# EEM_FMC_Carrier.net
KiCad netlist of a schematic drawn in Altium Designer
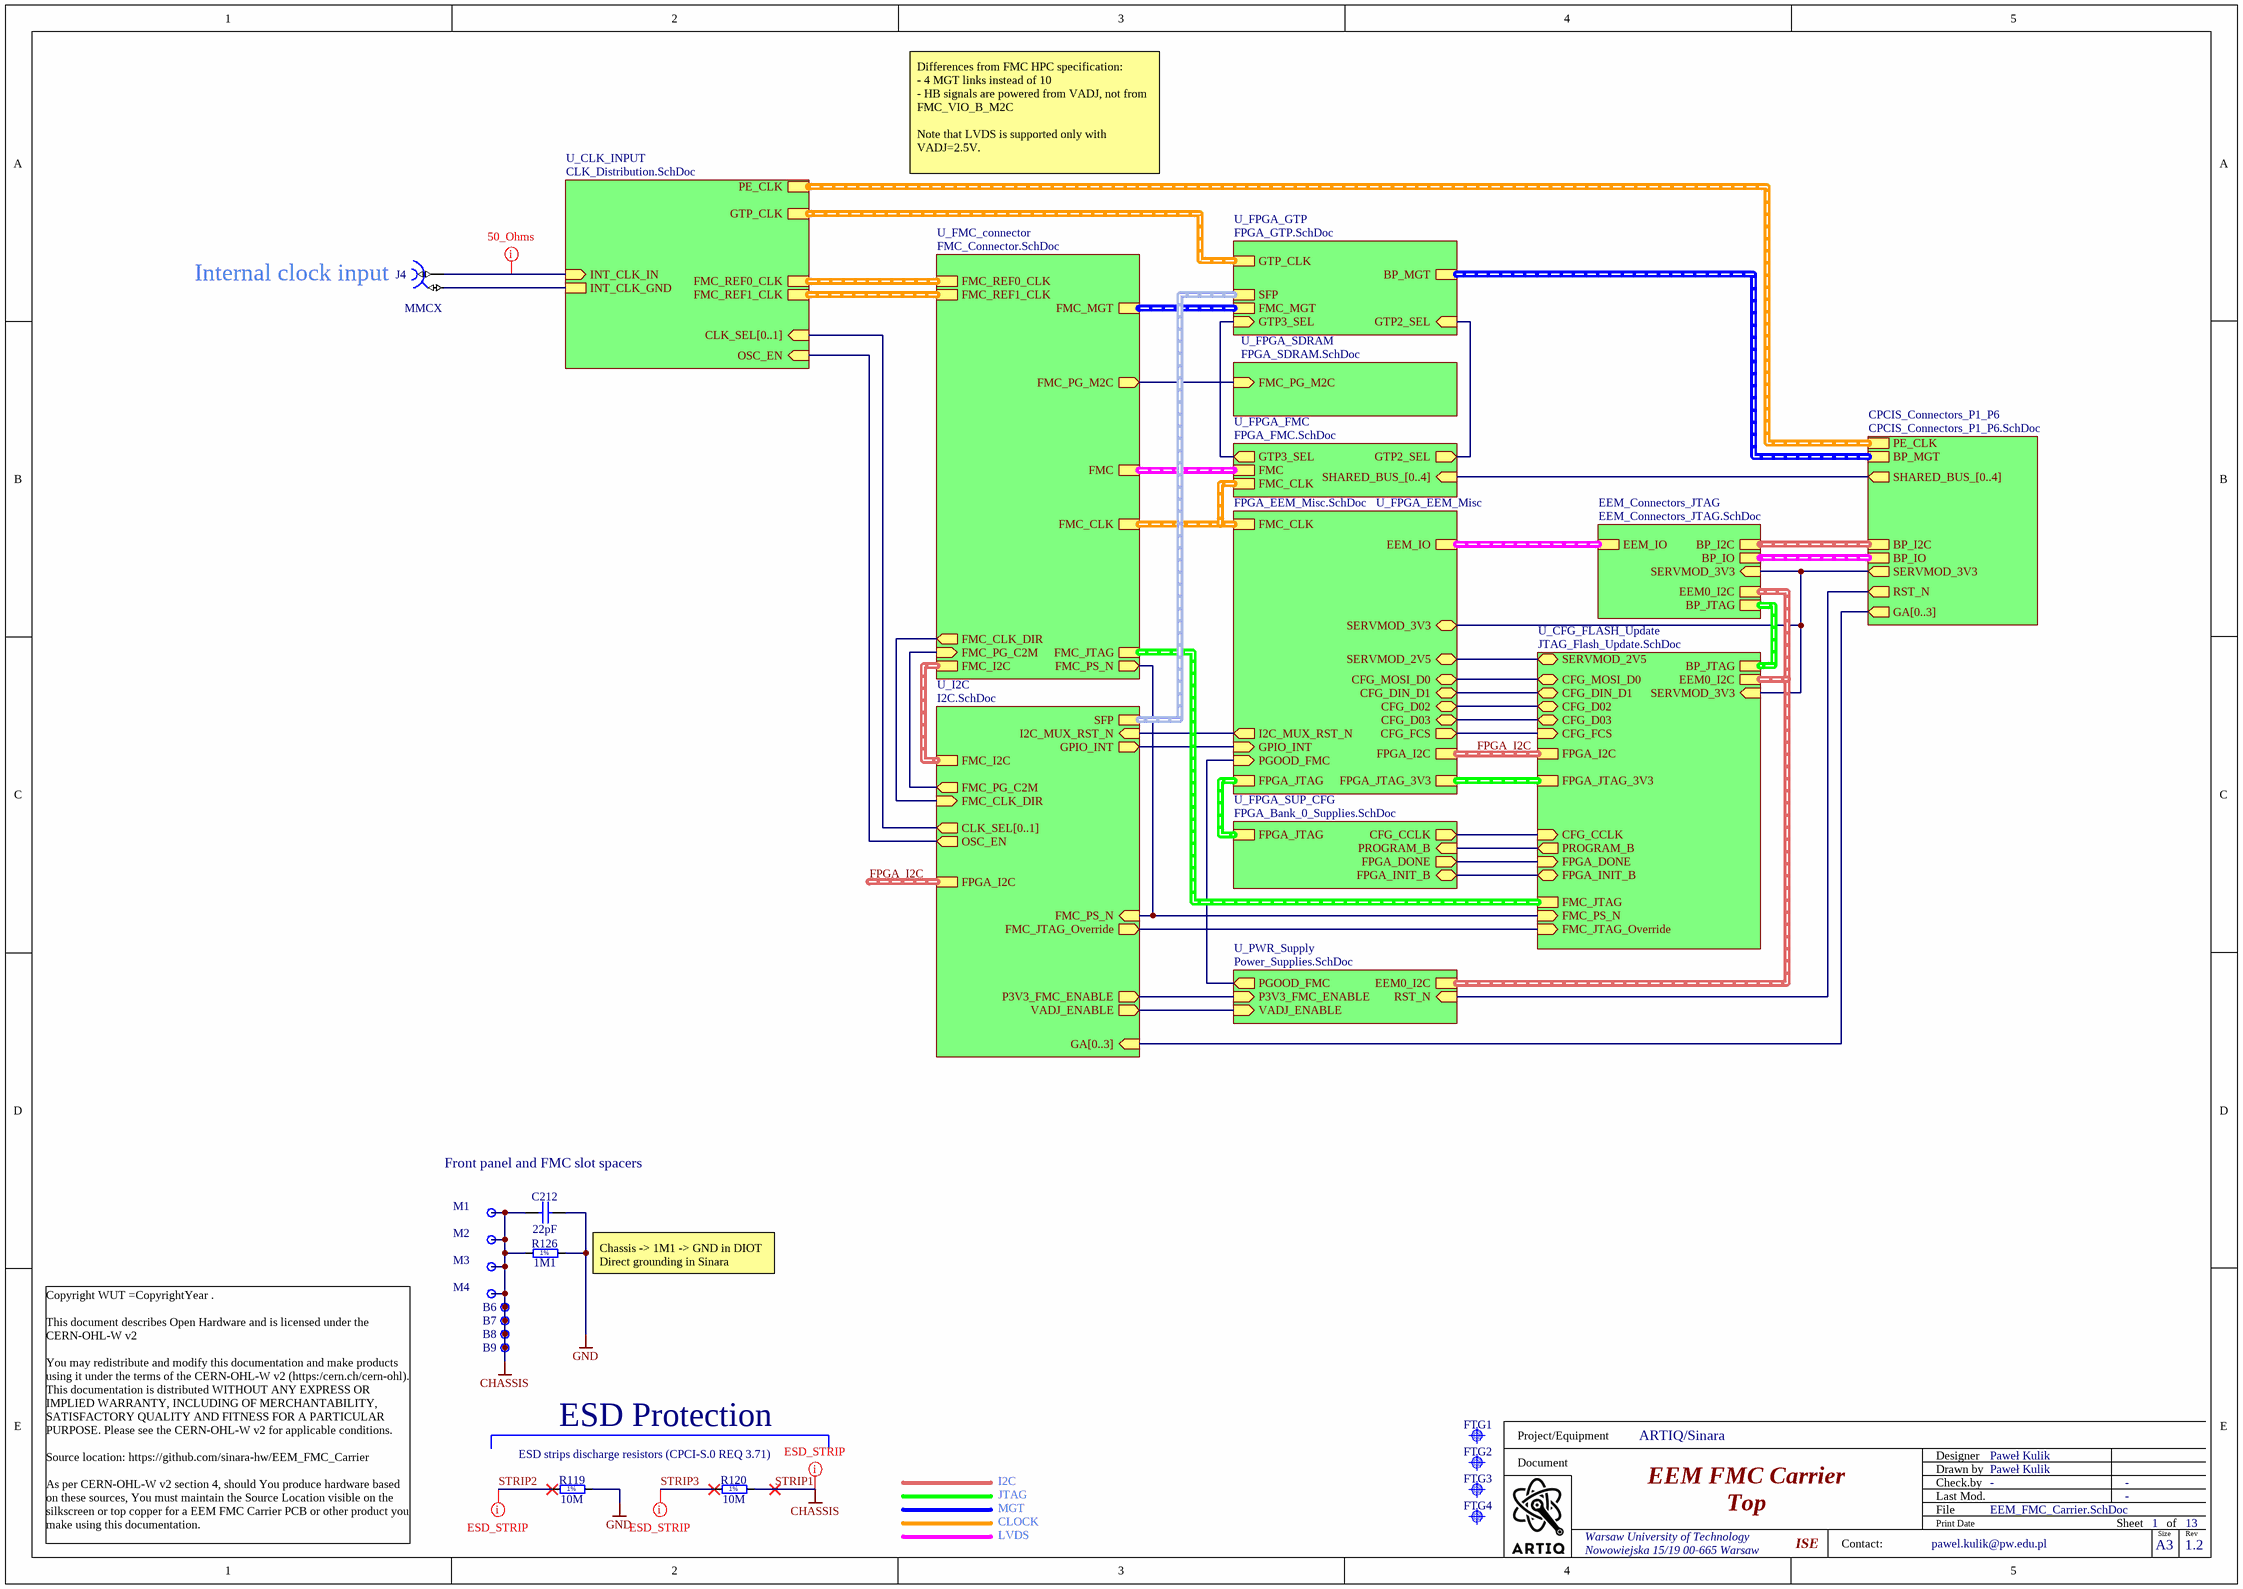
[diagram p0: EEM_FMC_Carrier.SchDoc]

(export (version "E")
  (design (tool "Eeschema 10.0.6"))
  (components
    (comp (ref "B6")
      (value "Plated Hole")
      (footprint "MTG270_500")
      (description "Single Terminal Socket")
      (fields (field (name "PART NUMBER") "PLATED_HOLE2.7_PAD5.0") (field (name "AUTHOR") "CERN DEM JMW"))
      (libsource (lib "Eletro-mechanical") (part "Single Terminal Socket"))
    )
    (comp (ref "B7")
      (value "Plated Hole")
      (footprint "MTG270_500")
      (description "Single Terminal Socket")
      (fields (field (name "PART NUMBER") "PLATED_HOLE2.7_PAD5.0") (field (name "AUTHOR") "CERN DEM JMW"))
      (libsource (lib "Eletro-mechanical") (part "Single Terminal Socket"))
    )
    (comp (ref "B8")
      (value "Plated Hole")
      (footprint "MTG270_500")
      (description "Single Terminal Socket")
      (fields (field (name "PART NUMBER") "PLATED_HOLE2.7_PAD5.0") (field (name "AUTHOR") "CERN DEM JMW"))
      (libsource (lib "Eletro-mechanical") (part "Single Terminal Socket"))
    )
    (comp (ref "B9")
      (value "Plated Hole")
      (footprint "MTG270_500")
      (description "Single Terminal Socket")
      (fields (field (name "PART NUMBER") "PLATED_HOLE2.7_PAD5.0") (field (name "AUTHOR") "CERN DEM JMW"))
      (libsource (lib "Eletro-mechanical") (part "Single Terminal Socket"))
    )
    (comp (ref "C212")
      (value "22pF")
      (footprint "CAPC1005X55N")
      (description "Non-polarised capacitor")
      (fields
        (field (name "PART NUMBER") "CC0402_22PF_50V_5%_C0G")
        (field (name "VOLTAGE") "50V")
        (field (name "AUTHOR") "CERN DEM JLC")
      )
      (libsource (lib "Capacitors") (part "Capacitor - non polarized"))
    )
    (comp (ref "FTG1")
      (value "Use only in PCB")
      (footprint "FIDUCIAL_TOP_C100-200")
      (description "Fiducial Target")
      (fields (field (name "PART NUMBER") "FIDUCIAL_TARGET_C100-200") (field (name "AUTHOR") "CERN DEM JLC"))
      (libsource (lib "Eletro-mechanical") (part "Fiducial Target"))
    )
    (comp (ref "FTG2")
      (value "Use only in PCB")
      (footprint "FIDUCIAL_TOP_S100-200")
      (description "Fiducial Target")
      (fields (field (name "PART NUMBER") "FIDUCIAL_TARGET_S100-200") (field (name "AUTHOR") "CERN DEM JLC"))
      (libsource (lib "Eletro-mechanical") (part "Fiducial Target"))
    )
    (comp (ref "FTG3")
      (value "Use only in PCB")
      (footprint "FIDUCIAL_TOP_S100-200")
      (description "Fiducial Target")
      (fields (field (name "PART NUMBER") "FIDUCIAL_TARGET_S100-200") (field (name "AUTHOR") "CERN DEM JLC"))
      (libsource (lib "Eletro-mechanical") (part "Fiducial Target"))
    )
    (comp (ref "FTG4")
      (value "Use only in PCB")
      (footprint "FIDUCIAL_TOP_S100-200")
      (description "Fiducial Target")
      (fields (field (name "PART NUMBER") "FIDUCIAL_TARGET_S100-200") (field (name "AUTHOR") "CERN DEM JLC"))
      (libsource (lib "Eletro-mechanical") (part "Fiducial Target"))
    )
    (comp (ref "J4")
      (value "MMCX")
      (footprint "SAMTEC_MMCX-J-P-H-ST-TH1")
      (fields
        (field (name "PART NUMBER") "SAMTEC_MMCX-J-P-H-ST-TH1")
        (field (name "MANUFACTURER") "SAMTEC")
        (field (name "MANUFACTURER PART NUMBER") "MMCX-J-P-H-ST-TH1")
        (field (name "AUTHOR") "CERN DEM JLC")
      )
      (libsource (lib "Connectors") (part "Coax_1Female_1Shield"))
    )
    (comp (ref "M1")
      (value "Plated Hole")
      (footprint "MTG300_600")
      (description "Single Terminal Socket")
      (fields (field (name "PART NUMBER") "PLATED_HOLE3.0_PAD6.0") (field (name "AUTHOR") "CERN DEM JLC"))
      (libsource (lib "Eletro-mechanical") (part "Single Terminal Socket"))
    )
    (comp (ref "M2")
      (value "Plated Hole")
      (footprint "MTG300_600")
      (description "Single Terminal Socket")
      (fields (field (name "PART NUMBER") "PLATED_HOLE3.0_PAD6.0") (field (name "AUTHOR") "CERN DEM JLC"))
      (libsource (lib "Eletro-mechanical") (part "Single Terminal Socket"))
    )
    (comp (ref "M3")
      (value "Plated Hole")
      (footprint "MTG300_600")
      (description "Single Terminal Socket")
      (fields (field (name "PART NUMBER") "PLATED_HOLE3.0_PAD6.0") (field (name "AUTHOR") "CERN DEM JLC"))
      (libsource (lib "Eletro-mechanical") (part "Single Terminal Socket"))
    )
    (comp (ref "M4")
      (value "Plated Hole")
      (footprint "MTG300_600")
      (description "Single Terminal Socket")
      (fields (field (name "PART NUMBER") "PLATED_HOLE3.0_PAD6.0") (field (name "AUTHOR") "CERN DEM JLC"))
      (libsource (lib "Eletro-mechanical") (part "Single Terminal Socket"))
    )
    (comp (ref "R119")
      (value "10M")
      (footprint "RESC2113X55N")
      (description "Resistor - 1%")
      (fields
        (field (name "PART NUMBER") "R0805_10M_1%_0.125W_100PPM_VISHAY_CRCW e3")
        (field (name "POWER") "0.125W")
        (field (name "AUTHOR") "CERN DEM BC")
      )
      (libsource (lib "Resistors") (part "Resistor - 1%"))
    )
    (comp (ref "R120")
      (value "10M")
      (footprint "RESC2113X55N")
      (description "Resistor - 1%")
      (fields
        (field (name "PART NUMBER") "R0805_10M_1%_0.125W_100PPM_VISHAY_CRCW e3")
        (field (name "POWER") "0.125W")
        (field (name "AUTHOR") "CERN DEM BC")
      )
      (libsource (lib "Resistors") (part "Resistor - 1%"))
    )
    (comp (ref "R126")
      (value "1M1")
      (footprint "RESC2012X60N")
      (description "Resistor - 1%")
      (fields
        (field (name "PART NUMBER") "R0805_1M1_1%_0.125W_100PPM")
        (field (name "MANUFACTURER") "GENERIC")
        (field (name "AUTHOR") "CERN DEM JLC")
      )
      (libsource (lib "Resistors") (part "Resistor - 1%"))
    )
  )
  (nets
    (net (code "37") (name "/INT_CLK_GND") (class "Default")
      (node (ref "J4") (pin "2") (pinfunction "2_2") (pintype "bidirectional"))
    )
    (net (code "38") (name "/INT_CLK_IN") (class "Default")
      (node (ref "J4") (pin "1") (pinfunction "1_1") (pintype "bidirectional"))
    )
    (net (code "50") (name "/STRIP2") (class "Default")
      (node (ref "R119") (pin "1") (pinfunction "1_1") (pintype "passive+no_connect"))
    )
    (net (code "51") (name "/STRIP3") (class "Default")
      (node (ref "R120") (pin "1") (pinfunction "1_1") (pintype "passive+no_connect"))
    )
    (net (code "54") (name "CHASSIS") (class "Default")
      (node (ref "B6") (pin "1") (pinfunction "1_1") (pintype "bidirectional"))
      (node (ref "B7") (pin "1") (pinfunction "1_1") (pintype "bidirectional"))
      (node (ref "B8") (pin "1") (pinfunction "1_1") (pintype "bidirectional"))
      (node (ref "B9") (pin "1") (pinfunction "1_1") (pintype "bidirectional"))
      (node (ref "C212") (pin "1") (pinfunction "1_1") (pintype "passive"))
      (node (ref "M1") (pin "1") (pinfunction "1_1") (pintype "bidirectional"))
      (node (ref "M2") (pin "1") (pinfunction "1_1") (pintype "bidirectional"))
      (node (ref "M3") (pin "1") (pinfunction "1_1") (pintype "bidirectional"))
      (node (ref "M4") (pin "1") (pinfunction "1_1") (pintype "bidirectional"))
      (node (ref "R120") (pin "2") (pinfunction "2_2") (pintype "passive"))
      (node (ref "R126") (pin "1") (pinfunction "1_1") (pintype "passive"))
    )
    (net (code "55") (name "GND") (class "Default")
      (node (ref "C212") (pin "2") (pinfunction "2_2") (pintype "passive"))
      (node (ref "R119") (pin "2") (pinfunction "2_2") (pintype "passive"))
      (node (ref "R126") (pin "2") (pinfunction "2_2") (pintype "passive"))
    )
  )
)
